# PIC16F690Sensor.net
KiCad netlist of a schematic drawn in Altium Designer
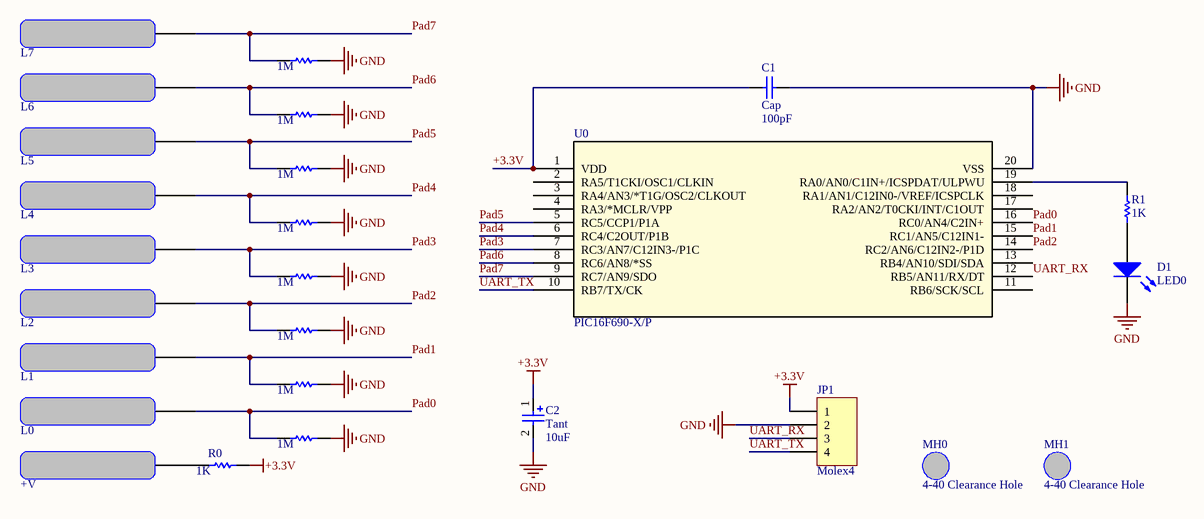
[diagram p0: PIC16F690Sensor.SchDoc]

(export (version "E")
  (design (tool "Eeschema 10.0.6"))
  (components
    (comp (ref "+V")
      (value "Water Pad")
      (footprint "WaterPad")
      (libsource (lib "PIC16F690_Schematic") (part "Water Pad"))
    )
    (comp (ref "C1")
      (value "Cap")
      (footprint "RAD-0.1")
      (description "Capacitor")
      (fields
        (field (name "MANUFACTURER") "Generic Components")
        (field (name "ALTIUM_VALUE") "100pF")
        (field (name "PUBLISHER") "Altium Hobart Technology Centre")
      )
      (libsource (lib "ME218_BaseLib") (part "Cap"))
    )
    (comp (ref "C2")
      (value "Tant")
      (footprint "10UF_TANTALUM NO CROSS")
      (description "Polarized Capacitor (Radial)")
      (fields
        (field (name "MANUFACTURER") "Generic Components")
        (field (name "ALTIUM_VALUE") "10uF")
        (field (name "PUBLISHER") "Altium Hobart Technology Centre")
      )
      (libsource (lib "ME218_BaseLib") (part "Cap Pol1"))
    )
    (comp (ref "D1")
      (value "LED0")
      (footprint "DIODE_SMALL")
      (description "Typical INFRARED GaAs LED")
      (fields (field (name "PUBLISHER") "Altium Limited"))
      (libsource (lib "Miscellaneous Devices") (part "LED0"))
    )
    (comp (ref "JP1")
      (value "Molex4")
      (footprint "MOLEX_4_PIN")
      (description "Header, 4-Pin")
      (fields (field (name "MANUFACTURER") "Generic Components"))
      (libsource (lib "ME218_BaseLib") (part "Molex4"))
    )
    (comp (ref "L0")
      (value "Water Pad")
      (footprint "WaterPad")
      (libsource (lib "PIC16F690_Schematic") (part "Water Pad"))
    )
    (comp (ref "L1")
      (value "Water Pad")
      (footprint "WaterPad")
      (libsource (lib "PIC16F690_Schematic") (part "Water Pad"))
    )
    (comp (ref "L2")
      (value "Water Pad")
      (footprint "WaterPad")
      (libsource (lib "PIC16F690_Schematic") (part "Water Pad"))
    )
    (comp (ref "L3")
      (value "Water Pad")
      (footprint "WaterPad")
      (libsource (lib "PIC16F690_Schematic") (part "Water Pad"))
    )
    (comp (ref "L4")
      (value "Water Pad")
      (footprint "WaterPad")
      (libsource (lib "PIC16F690_Schematic") (part "Water Pad"))
    )
    (comp (ref "L5")
      (value "Water Pad")
      (footprint "WaterPad")
      (libsource (lib "PIC16F690_Schematic") (part "Water Pad"))
    )
    (comp (ref "L6")
      (value "Water Pad")
      (footprint "WaterPad")
      (libsource (lib "PIC16F690_Schematic") (part "Water Pad"))
    )
    (comp (ref "L7")
      (value "Water Pad")
      (footprint "WaterPad")
      (libsource (lib "PIC16F690_Schematic") (part "Water Pad"))
    )
    (comp (ref "MH0")
      (value "4-40 Clearance Hole")
      (footprint "4-40 Clearance Hole")
      (libsource (lib "ME218D_GM_2017") (part "4-40 Clearance Hole"))
    )
    (comp (ref "MH1")
      (value "4-40 Clearance Hole")
      (footprint "4-40 Clearance Hole")
      (libsource (lib "ME218D_GM_2017") (part "4-40 Clearance Hole"))
    )
    (comp (ref "R0")
      (value "1K")
      (footprint "Resistor-0.1")
      (description "Resistor")
      (fields (field (name "Comment") "Res1") (field (name "PUBLISHER") "Altium Limited"))
      (libsource (lib "Miscellaneous Devices") (part "Res1"))
    )
    (comp (ref "R1")
      (value "1K")
      (footprint "Resistor-0.1")
      (description "Resistor")
      (fields (field (name "Comment") "Res1") (field (name "PUBLISHER") "Altium Limited"))
      (libsource (lib "Miscellaneous Devices") (part "Res1"))
    )
    (comp (ref "R2")
      (value "1M")
      (footprint "Resistor-0.1")
      (description "Resistor")
      (fields (field (name "Comment") "R2") (field (name "PUBLISHER") "Altium Limited"))
      (libsource (lib "Miscellaneous Devices") (part "Res1"))
    )
    (comp (ref "R3")
      (value "1M")
      (footprint "Resistor-0.1")
      (description "Resistor")
      (fields (field (name "Comment") "Res1") (field (name "PUBLISHER") "Altium Limited"))
      (libsource (lib "Miscellaneous Devices") (part "Res1"))
    )
    (comp (ref "R4")
      (value "1M")
      (footprint "Resistor-0.1")
      (description "Resistor")
      (fields (field (name "Comment") "Res1") (field (name "PUBLISHER") "Altium Limited"))
      (libsource (lib "Miscellaneous Devices") (part "Res1"))
    )
    (comp (ref "R5")
      (value "1M")
      (footprint "Resistor-0.1")
      (description "Resistor")
      (fields (field (name "Comment") "Res1") (field (name "PUBLISHER") "Altium Limited"))
      (libsource (lib "Miscellaneous Devices") (part "Res1"))
    )
    (comp (ref "R6")
      (value "1M")
      (footprint "Resistor-0.1")
      (description "Resistor")
      (fields (field (name "Comment") "Res1") (field (name "PUBLISHER") "Altium Limited"))
      (libsource (lib "Miscellaneous Devices") (part "Res1"))
    )
    (comp (ref "R7")
      (value "1M")
      (footprint "Resistor-0.1")
      (description "Resistor")
      (fields (field (name "Comment") "Res1") (field (name "PUBLISHER") "Altium Limited"))
      (libsource (lib "Miscellaneous Devices") (part "Res1"))
    )
    (comp (ref "R8")
      (value "1M")
      (footprint "Resistor-0.1")
      (description "Resistor")
      (fields (field (name "Comment") "Res1") (field (name "PUBLISHER") "Altium Limited"))
      (libsource (lib "Miscellaneous Devices") (part "Res1"))
    )
    (comp (ref "R9")
      (value "1M")
      (footprint "Resistor-0.1")
      (description "Resistor")
      (fields (field (name "Comment") "Res1") (field (name "PUBLISHER") "Altium Limited"))
      (libsource (lib "Miscellaneous Devices") (part "Res1"))
    )
    (comp (ref "U0")
      (value "PIC16F690-X/P")
      (footprint "DIP-20-KEY")
      (description "Imported")
      (libsource (lib "PIC16F690_Schematic") (part "PIC16F690-X/P"))
    )
  )
  (nets
    (net (code "1") (name "+3.3V") (class "Default")
      (node (ref "C1") (pin "2") (pinfunction "2_2") (pintype "passive"))
      (node (ref "C2") (pin "1") (pinfunction "1_1") (pintype "power_in"))
      (node (ref "JP1") (pin "1") (pinfunction "1_1") (pintype "passive"))
      (node (ref "R0") (pin "2") (pinfunction "2_2") (pintype "passive"))
      (node (ref "U0") (pin "1") (pinfunction "VDD_1") (pintype "passive"))
    )
    (net (code "2") (name "/Pad0") (class "Default")
      (node (ref "L0") (pin "0") (pinfunction "0_0") (pintype "passive"))
      (node (ref "R2") (pin "1") (pinfunction "1_1") (pintype "passive"))
      (node (ref "U0") (pin "16") (pinfunction "RC0/AN4/C2IN+_16") (pintype "passive"))
    )
    (net (code "3") (name "/Pad1") (class "Default")
      (node (ref "L1") (pin "0") (pinfunction "0_0") (pintype "passive"))
      (node (ref "R3") (pin "1") (pinfunction "1_1") (pintype "passive"))
      (node (ref "U0") (pin "15") (pinfunction "RC1/AN5/C12IN1-_15") (pintype "passive"))
    )
    (net (code "4") (name "/Pad2") (class "Default")
      (node (ref "L2") (pin "0") (pinfunction "0_0") (pintype "passive"))
      (node (ref "R4") (pin "1") (pinfunction "1_1") (pintype "passive"))
      (node (ref "U0") (pin "14") (pinfunction "RC2/AN6/C12IN2-/P1D_14") (pintype "passive"))
    )
    (net (code "5") (name "/Pad3") (class "Default")
      (node (ref "L3") (pin "0") (pinfunction "0_0") (pintype "passive"))
      (node (ref "R5") (pin "1") (pinfunction "1_1") (pintype "passive"))
      (node (ref "U0") (pin "7") (pinfunction "RC3/AN7/C12IN3-/P1C_7") (pintype "passive"))
    )
    (net (code "6") (name "/Pad4") (class "Default")
      (node (ref "L4") (pin "0") (pinfunction "0_0") (pintype "passive"))
      (node (ref "R6") (pin "1") (pinfunction "1_1") (pintype "passive"))
      (node (ref "U0") (pin "6") (pinfunction "RC4/C2OUT/P1B_6") (pintype "passive"))
    )
    (net (code "7") (name "/Pad5") (class "Default")
      (node (ref "L5") (pin "0") (pinfunction "0_0") (pintype "passive"))
      (node (ref "R7") (pin "1") (pinfunction "1_1") (pintype "passive"))
      (node (ref "U0") (pin "5") (pinfunction "RC5/CCP1/P1A_5") (pintype "passive"))
    )
    (net (code "8") (name "/Pad6") (class "Default")
      (node (ref "L6") (pin "0") (pinfunction "0_0") (pintype "passive"))
      (node (ref "R8") (pin "1") (pinfunction "1_1") (pintype "passive"))
      (node (ref "U0") (pin "8") (pinfunction "RC6/AN8/*SS_8") (pintype "passive"))
    )
    (net (code "9") (name "/Pad7") (class "Default")
      (node (ref "L7") (pin "0") (pinfunction "0_0") (pintype "passive"))
      (node (ref "R9") (pin "1") (pinfunction "1_1") (pintype "passive"))
      (node (ref "U0") (pin "9") (pinfunction "RC7/AN9/SDO_9") (pintype "passive"))
    )
    (net (code "10") (name "/UART_RX") (class "Default")
      (node (ref "JP1") (pin "3") (pinfunction "3_3") (pintype "passive"))
      (node (ref "U0") (pin "12") (pinfunction "RB5/AN11/RX/DT_12") (pintype "passive"))
    )
    (net (code "11") (name "/UART_TX") (class "Default")
      (node (ref "JP1") (pin "4") (pinfunction "4_4") (pintype "passive"))
      (node (ref "U0") (pin "10") (pinfunction "RB7/TX/CK_10") (pintype "passive"))
    )
    (net (code "12") (name "GND") (class "Default")
      (node (ref "C1") (pin "1") (pinfunction "1_1") (pintype "passive"))
      (node (ref "C2") (pin "2") (pinfunction "2_2") (pintype "power_in"))
      (node (ref "D1") (pin "2") (pinfunction "K_2") (pintype "passive"))
      (node (ref "JP1") (pin "2") (pinfunction "2_2") (pintype "passive"))
      (node (ref "R2") (pin "2") (pinfunction "2_2") (pintype "passive"))
      (node (ref "R3") (pin "2") (pinfunction "2_2") (pintype "passive"))
      (node (ref "R4") (pin "2") (pinfunction "2_2") (pintype "passive"))
      (node (ref "R5") (pin "2") (pinfunction "2_2") (pintype "passive"))
      (node (ref "R6") (pin "2") (pinfunction "2_2") (pintype "passive"))
      (node (ref "R7") (pin "2") (pinfunction "2_2") (pintype "passive"))
      (node (ref "R8") (pin "2") (pinfunction "2_2") (pintype "passive"))
      (node (ref "R9") (pin "2") (pinfunction "2_2") (pintype "passive"))
      (node (ref "U0") (pin "20") (pinfunction "VSS_20") (pintype "passive"))
    )
    (net (code "13") (name "Net-(+V-Pad0)") (class "Default")
      (node (ref "+V") (pin "0") (pinfunction "0_0") (pintype "passive"))
      (node (ref "R0") (pin "1") (pinfunction "1_1") (pintype "passive"))
    )
    (net (code "14") (name "Net-(D1-A)") (class "Default")
      (node (ref "D1") (pin "1") (pinfunction "A_1") (pintype "passive"))
      (node (ref "R1") (pin "1") (pinfunction "1_1") (pintype "passive"))
    )
    (net (code "15") (name "Net-(U0-RA0{slash}AN0{slash}C1IN+{slash}ICSPDAT{slash}ULPWU)") (class "Default")
      (node (ref "R1") (pin "2") (pinfunction "2_2") (pintype "passive"))
      (node (ref "U0") (pin "19") (pinfunction "RA0/AN0/C1IN+/ICSPDAT/ULPWU_19") (pintype "passive"))
    )
    (net (code "16") (name "unconnected-(U0-RA1{slash}AN1{slash}C12IN0-{slash}VREF{slash}ICSPCLK-Pad18)") (class "Default")
      (node (ref "U0") (pin "18") (pinfunction "RA1/AN1/C12IN0-/VREF/ICSPCLK_18") (pintype "passive"))
    )
    (net (code "17") (name "unconnected-(U0-RA2{slash}AN2{slash}T0CKI{slash}INT{slash}C1OUT-Pad17)") (class "Default")
      (node (ref "U0") (pin "17") (pinfunction "RA2/AN2/T0CKI/INT/C1OUT_17") (pintype "passive"))
    )
    (net (code "18") (name "unconnected-(U0-RA3{slash}*MCLR{slash}VPP-Pad4)") (class "Default")
      (node (ref "U0") (pin "4") (pinfunction "RA3/*MCLR/VPP_4") (pintype "passive"))
    )
    (net (code "19") (name "unconnected-(U0-RA4{slash}AN3{slash}*T1G{slash}OSC2{slash}CLKOUT-Pad3)") (class "Default")
      (node (ref "U0") (pin "3") (pinfunction "RA4/AN3/*T1G/OSC2/CLKOUT_3") (pintype "passive"))
    )
    (net (code "20") (name "unconnected-(U0-RA5{slash}T1CKI{slash}OSC1{slash}CLKIN-Pad2)") (class "Default")
      (node (ref "U0") (pin "2") (pinfunction "RA5/T1CKI/OSC1/CLKIN_2") (pintype "passive"))
    )
    (net (code "21") (name "unconnected-(U0-RB4{slash}AN10{slash}SDI{slash}SDA-Pad13)") (class "Default")
      (node (ref "U0") (pin "13") (pinfunction "RB4/AN10/SDI/SDA_13") (pintype "passive"))
    )
    (net (code "22") (name "unconnected-(U0-RB6{slash}SCK{slash}SCL-Pad11)") (class "Default")
      (node (ref "U0") (pin "11") (pinfunction "RB6/SCK/SCL_11") (pintype "passive"))
    )
  )
)
